# daclock-1_2.net
KiCad netlist of a schematic drawn in EAGLE
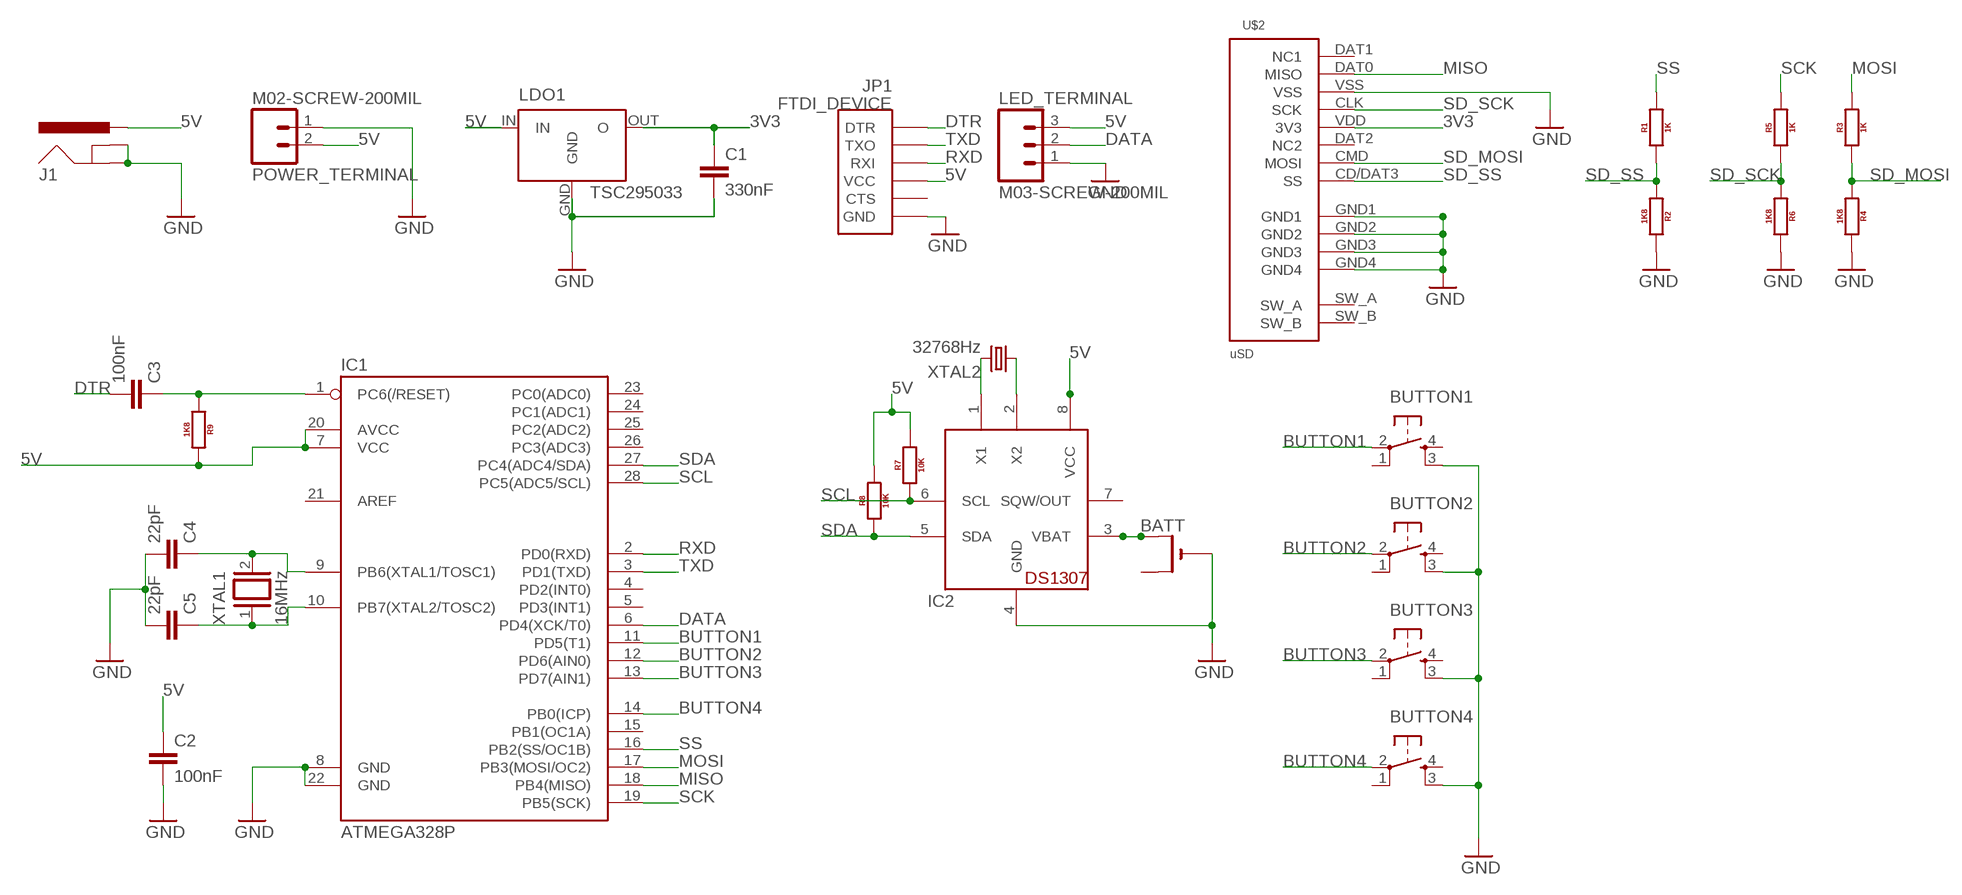
[diagram p0: schematic, sheet 1]

(export (version "E")
  (design (tool "Eeschema 10.0.6"))
  (components
    (comp (ref "BATT")
      (value "CR2032SMT")
      (footprint "eagle-import:CR2032-SMD")
      (libsource (lib "eagle-import") (part "CR2032SMT"))
    )
    (comp (ref "BUTTON1")
      (value "B1")
      (footprint "eagle-import:TACTILE_BUTTON")
      (libsource (lib "eagle-import") (part "TACTILE_BUTTON"))
    )
    (comp (ref "BUTTON2")
      (value "B2")
      (footprint "eagle-import:TACTILE_BUTTON")
      (libsource (lib "eagle-import") (part "TACTILE_BUTTON"))
    )
    (comp (ref "BUTTON3")
      (value "B3")
      (footprint "eagle-import:TACTILE_BUTTON")
      (libsource (lib "eagle-import") (part "TACTILE_BUTTON"))
    )
    (comp (ref "BUTTON4")
      (value "B4")
      (footprint "eagle-import:TACTILE_BUTTON")
      (libsource (lib "eagle-import") (part "TACTILE_BUTTON"))
    )
    (comp (ref "C1")
      (value "330nF")
      (footprint "eagle-import:C050-025X075")
      (libsource (lib "eagle-import") (part "C-EU050-025X075"))
    )
    (comp (ref "C2")
      (value "100nF")
      (footprint "eagle-import:C050-025X075")
      (libsource (lib "eagle-import") (part "C-EU050-025X075"))
    )
    (comp (ref "C3")
      (value "100nF")
      (footprint "eagle-import:C050-025X075")
      (libsource (lib "eagle-import") (part "C-EU050-025X075"))
    )
    (comp (ref "C4")
      (value "22pF")
      (footprint "eagle-import:C050-025X075")
      (libsource (lib "eagle-import") (part "C-EU050-025X075"))
    )
    (comp (ref "C5")
      (value "22pF")
      (footprint "eagle-import:C050-025X075")
      (libsource (lib "eagle-import") (part "C-EU050-025X075"))
    )
    (comp (ref "IC1")
      (value "ATMEGA328P")
      (footprint "eagle-import:DIL28-3")
      (libsource (lib "eagle-import") (part "ATMEGA328P_PDIP"))
    )
    (comp (ref "IC2")
      (value "DS1307")
      (footprint "eagle-import:DIL08")
      (libsource (lib "eagle-import") (part "DS1307"))
    )
    (comp (ref "J1")
      (value "POWER_JACKPTH")
      (footprint "eagle-import:POWER_JACK_PTH")
      (libsource (lib "eagle-import") (part "POWER_JACKPTH"))
    )
    (comp (ref "JP1")
      (value "FTDI_DEVICE")
      (footprint "eagle-import:FTDI_DEVICE_SIDE")
      (libsource (lib "eagle-import") (part "FTDI_DEVICE"))
    )
    (comp (ref "LDO1")
      (value "TSC295033")
      (footprint "eagle-import:TO92")
      (fields (field (name "MF") "NATIONAL SEMICONDUCTOR") (field (name "MPN") "LP2950CZ-5.0/NOPB"))
      (libsource (lib "eagle-import") (part "LP2950Z"))
    )
    (comp (ref "LED_TERMINAL")
      (value "M03-SCREW-200MIL")
      (footprint "eagle-import:SCREWTERMINAL-200MIL-3")
      (libsource (lib "eagle-import") (part "M03-SCREW-200MIL"))
    )
    (comp (ref "POWER_TERMINAL")
      (value "M02-SCREW-200MIL")
      (footprint "eagle-import:SCREWTERMINAL-200MIL-2")
      (libsource (lib "eagle-import") (part "M02-SCREW-200MIL"))
    )
    (comp (ref "R1")
      (value "1K")
      (footprint "eagle-import:AXIAL-0.4")
      (libsource (lib "eagle-import") (part "RESISTOR-400MIL"))
    )
    (comp (ref "R2")
      (value "1K8")
      (footprint "eagle-import:AXIAL-0.4")
      (libsource (lib "eagle-import") (part "RESISTOR-400MIL"))
    )
    (comp (ref "R3")
      (value "1K")
      (footprint "eagle-import:AXIAL-0.4")
      (libsource (lib "eagle-import") (part "RESISTOR-400MIL"))
    )
    (comp (ref "R4")
      (value "1K8")
      (footprint "eagle-import:AXIAL-0.4")
      (libsource (lib "eagle-import") (part "RESISTOR-400MIL"))
    )
    (comp (ref "R5")
      (value "1K")
      (footprint "eagle-import:AXIAL-0.4")
      (libsource (lib "eagle-import") (part "RESISTOR-400MIL"))
    )
    (comp (ref "R6")
      (value "1K8")
      (footprint "eagle-import:AXIAL-0.4")
      (libsource (lib "eagle-import") (part "RESISTOR-400MIL"))
    )
    (comp (ref "R7")
      (value "10K")
      (footprint "eagle-import:AXIAL-0.4")
      (libsource (lib "eagle-import") (part "RESISTOR-400MIL"))
    )
    (comp (ref "R8")
      (value "10K")
      (footprint "eagle-import:AXIAL-0.4")
      (libsource (lib "eagle-import") (part "RESISTOR-400MIL"))
    )
    (comp (ref "R9")
      (value "1K8")
      (footprint "eagle-import:AXIAL-0.4")
      (libsource (lib "eagle-import") (part "RESISTOR-400MIL"))
    )
    (comp (ref "U$2")
      (value "uSD")
      (footprint "eagle-import:DM3D")
      (libsource (lib "eagle-import") (part "MICROSD-HRS_DM3D"))
    )
    (comp (ref "XTAL1")
      (value "16MHz")
      (footprint "eagle-import:QS")
      (libsource (lib "eagle-import") (part "XTAL/S"))
    )
    (comp (ref "XTAL2")
      (value "32768Hz")
      (footprint "eagle-import:TC38H")
      (libsource (lib "eagle-import") (part "CRYSTAL_TC38H"))
    )
  )
  (nets
    (net (code "1") (name "/3V3") (class "Default")
      (node (ref "C1") (pin "1") (pinfunction "1_1") (pintype "passive"))
      (node (ref "LDO1") (pin "OUT") (pinfunction "O_OUT") (pintype "output"))
      (node (ref "U$2") (pin "VDD") (pinfunction "3V3_VDD") (pintype "bidirectional"))
    )
    (net (code "2") (name "/5V") (class "Default")
      (node (ref "C2") (pin "1") (pinfunction "1_1") (pintype "passive"))
      (node (ref "IC1") (pin "20") (pinfunction "AVCC_20") (pintype "bidirectional"))
      (node (ref "IC1") (pin "7") (pinfunction "VCC_7") (pintype "bidirectional"))
      (node (ref "IC2") (pin "8") (pinfunction "VCC_8") (pintype "power_in"))
      (node (ref "J1") (pin "PWR") (pinfunction "PWR_PWR") (pintype "bidirectional"))
      (node (ref "JP1") (pin "P$4") (pinfunction "VCC_P$4") (pintype "bidirectional"))
      (node (ref "LDO1") (pin "IN") (pinfunction "IN_IN") (pintype "input"))
      (node (ref "LED_TERMINAL") (pin "3") (pinfunction "3_3") (pintype "passive"))
      (node (ref "POWER_TERMINAL") (pin "2") (pinfunction "2_2") (pintype "passive"))
      (node (ref "R7") (pin "P$2") (pinfunction "2_P$2") (pintype "passive"))
      (node (ref "R8") (pin "P$2") (pinfunction "2_P$2") (pintype "passive"))
      (node (ref "R9") (pin "P$2") (pinfunction "2_P$2") (pintype "passive"))
    )
    (net (code "3") (name "/BUTTON1") (class "Default")
      (node (ref "BUTTON1") (pin "2") (pinfunction "SWA1_2") (pintype "passive"))
      (node (ref "IC1") (pin "11") (pinfunction "PD5(T1)_11") (pintype "bidirectional"))
    )
    (net (code "4") (name "/BUTTON2") (class "Default")
      (node (ref "BUTTON2") (pin "2") (pinfunction "SWA1_2") (pintype "passive"))
      (node (ref "IC1") (pin "12") (pinfunction "PD6(AIN0)_12") (pintype "bidirectional"))
    )
    (net (code "5") (name "/BUTTON3") (class "Default")
      (node (ref "BUTTON3") (pin "2") (pinfunction "SWA1_2") (pintype "passive"))
      (node (ref "IC1") (pin "13") (pinfunction "PD7(AIN1)_13") (pintype "bidirectional"))
    )
    (net (code "6") (name "/BUTTON4") (class "Default")
      (node (ref "BUTTON4") (pin "2") (pinfunction "SWA1_2") (pintype "passive"))
      (node (ref "IC1") (pin "14") (pinfunction "PB0(ICP)_14") (pintype "bidirectional"))
    )
    (net (code "7") (name "/DATA") (class "Default")
      (node (ref "IC1") (pin "6") (pinfunction "PD4(XCK/T0)_6") (pintype "bidirectional"))
      (node (ref "LED_TERMINAL") (pin "2") (pinfunction "2_2") (pintype "passive"))
    )
    (net (code "8") (name "/DTR") (class "Default")
      (node (ref "C3") (pin "2") (pinfunction "2_2") (pintype "passive"))
      (node (ref "JP1") (pin "P$1") (pinfunction "DTR_P$1") (pintype "bidirectional"))
    )
    (net (code "9") (name "/MISO") (class "Default")
      (node (ref "IC1") (pin "18") (pinfunction "PB4(MISO)_18") (pintype "bidirectional"))
      (node (ref "U$2") (pin "DAT0") (pinfunction "MISO_DAT0") (pintype "bidirectional"))
    )
    (net (code "10") (name "/MOSI") (class "Default")
      (node (ref "IC1") (pin "17") (pinfunction "PB3(MOSI/OC2)_17") (pintype "bidirectional"))
      (node (ref "R3") (pin "P$2") (pinfunction "2_P$2") (pintype "passive"))
    )
    (net (code "11") (name "/RXD") (class "Default")
      (node (ref "IC1") (pin "2") (pinfunction "PD0(RXD)_2") (pintype "bidirectional"))
      (node (ref "JP1") (pin "P$3") (pinfunction "RXI_P$3") (pintype "bidirectional"))
    )
    (net (code "12") (name "/SCK") (class "Default")
      (node (ref "IC1") (pin "19") (pinfunction "PB5(SCK)_19") (pintype "bidirectional"))
      (node (ref "R5") (pin "P$2") (pinfunction "2_P$2") (pintype "passive"))
    )
    (net (code "13") (name "/SCL") (class "Default")
      (node (ref "IC1") (pin "28") (pinfunction "PC5(ADC5/SCL)_28") (pintype "bidirectional"))
      (node (ref "IC2") (pin "6") (pinfunction "SCL_6") (pintype "bidirectional"))
      (node (ref "R7") (pin "P$1") (pinfunction "1_P$1") (pintype "passive"))
    )
    (net (code "14") (name "/SDA") (class "Default")
      (node (ref "IC1") (pin "27") (pinfunction "PC4(ADC4/SDA)_27") (pintype "bidirectional"))
      (node (ref "IC2") (pin "5") (pinfunction "SDA_5") (pintype "bidirectional"))
      (node (ref "R8") (pin "P$1") (pinfunction "1_P$1") (pintype "passive"))
    )
    (net (code "15") (name "/SD_MOSI") (class "Default")
      (node (ref "R3") (pin "P$1") (pinfunction "1_P$1") (pintype "passive"))
      (node (ref "R4") (pin "P$1") (pinfunction "1_P$1") (pintype "passive"))
      (node (ref "U$2") (pin "CMD") (pinfunction "MOSI_CMD") (pintype "bidirectional"))
    )
    (net (code "16") (name "/SD_SCK") (class "Default")
      (node (ref "R5") (pin "P$1") (pinfunction "1_P$1") (pintype "passive"))
      (node (ref "R6") (pin "P$1") (pinfunction "1_P$1") (pintype "passive"))
      (node (ref "U$2") (pin "CLK") (pinfunction "SCK_CLK") (pintype "bidirectional"))
    )
    (net (code "17") (name "/SD_SS") (class "Default")
      (node (ref "R1") (pin "P$1") (pinfunction "1_P$1") (pintype "passive"))
      (node (ref "R2") (pin "P$1") (pinfunction "1_P$1") (pintype "passive"))
      (node (ref "U$2") (pin "CD/DAT3") (pinfunction "SS_CD/DAT3") (pintype "bidirectional"))
    )
    (net (code "18") (name "/SS") (class "Default")
      (node (ref "IC1") (pin "16") (pinfunction "PB2(SS/OC1B)_16") (pintype "bidirectional"))
      (node (ref "R1") (pin "P$2") (pinfunction "2_P$2") (pintype "passive"))
    )
    (net (code "19") (name "/TXD") (class "Default")
      (node (ref "IC1") (pin "3") (pinfunction "PD1(TXD)_3") (pintype "bidirectional"))
      (node (ref "JP1") (pin "P$2") (pinfunction "TXO_P$2") (pintype "bidirectional"))
    )
    (net (code "20") (name "GND") (class "Default")
      (node (ref "BATT") (pin "-") (pinfunction "-_-") (pintype "passive"))
      (node (ref "BUTTON1") (pin "3") (pinfunction "SWB2_3") (pintype "passive"))
      (node (ref "BUTTON2") (pin "3") (pinfunction "SWB2_3") (pintype "passive"))
      (node (ref "BUTTON3") (pin "3") (pinfunction "SWB2_3") (pintype "passive"))
      (node (ref "BUTTON4") (pin "3") (pinfunction "SWB2_3") (pintype "passive"))
      (node (ref "C1") (pin "2") (pinfunction "2_2") (pintype "passive"))
      (node (ref "C2") (pin "2") (pinfunction "2_2") (pintype "passive"))
      (node (ref "C4") (pin "2") (pinfunction "2_2") (pintype "passive"))
      (node (ref "C5") (pin "2") (pinfunction "2_2") (pintype "passive"))
      (node (ref "IC1") (pin "22") (pinfunction "GND_22") (pintype "bidirectional"))
      (node (ref "IC1") (pin "8") (pinfunction "GND_8") (pintype "bidirectional"))
      (node (ref "IC2") (pin "4") (pinfunction "GND_4") (pintype "power_in"))
      (node (ref "J1") (pin "GND") (pinfunction "GND_GND") (pintype "bidirectional"))
      (node (ref "J1") (pin "GNDBREAK") (pinfunction "GNDBREAK_GNDBREAK") (pintype "bidirectional"))
      (node (ref "JP1") (pin "P$6") (pinfunction "GND_P$6") (pintype "bidirectional"))
      (node (ref "LDO1") (pin "GND") (pinfunction "GND_GND") (pintype "power_in"))
      (node (ref "LED_TERMINAL") (pin "1") (pinfunction "1_1") (pintype "passive"))
      (node (ref "POWER_TERMINAL") (pin "1") (pinfunction "1_1") (pintype "passive"))
      (node (ref "R2") (pin "P$2") (pinfunction "2_P$2") (pintype "passive"))
      (node (ref "R4") (pin "P$2") (pinfunction "2_P$2") (pintype "passive"))
      (node (ref "R6") (pin "P$2") (pinfunction "2_P$2") (pintype "passive"))
      (node (ref "U$2") (pin "GND1") (pinfunction "GND1_GND1") (pintype "bidirectional"))
      (node (ref "U$2") (pin "GND2") (pinfunction "GND2_GND2") (pintype "bidirectional"))
      (node (ref "U$2") (pin "GND3") (pinfunction "GND3_GND3") (pintype "bidirectional"))
      (node (ref "U$2") (pin "GND4") (pinfunction "GND4_GND4") (pintype "bidirectional"))
      (node (ref "U$2") (pin "VSS") (pinfunction "VSS_VSS") (pintype "bidirectional"))
    )
    (net (code "21") (name "Net-(BATT-+)") (class "Default")
      (node (ref "BATT") (pin "+$1") (pinfunction "+_+$1") (pintype "passive"))
      (node (ref "IC2") (pin "3") (pinfunction "VBAT_3") (pintype "power_in"))
    )
    (net (code "22") (name "Net-(IC1-PB6(XTAL1{slash}TOSC1))") (class "Default")
      (node (ref "C4") (pin "1") (pinfunction "1_1") (pintype "passive"))
      (node (ref "IC1") (pin "9") (pinfunction "PB6(XTAL1/TOSC1)_9") (pintype "bidirectional"))
      (node (ref "XTAL1") (pin "2") (pinfunction "2_2") (pintype "passive"))
    )
    (net (code "23") (name "Net-(IC1-PB7(XTAL2{slash}TOSC2))") (class "Default")
      (node (ref "C5") (pin "1") (pinfunction "1_1") (pintype "passive"))
      (node (ref "IC1") (pin "10") (pinfunction "PB7(XTAL2/TOSC2)_10") (pintype "bidirectional"))
      (node (ref "XTAL1") (pin "1") (pinfunction "1_1") (pintype "passive"))
    )
    (net (code "24") (name "Net-(IC1-PC6({slash}RESET))") (class "Default")
      (node (ref "C3") (pin "1") (pinfunction "1_1") (pintype "passive"))
      (node (ref "IC1") (pin "1") (pinfunction "PC6(/RESET)_1") (pintype "bidirectional"))
      (node (ref "R9") (pin "P$1") (pinfunction "1_P$1") (pintype "passive"))
    )
    (net (code "25") (name "Net-(IC2-X1)") (class "Default")
      (node (ref "IC2") (pin "1") (pinfunction "X1_1") (pintype "passive"))
      (node (ref "XTAL2") (pin "2") (pinfunction "2_2") (pintype "passive"))
    )
    (net (code "26") (name "Net-(IC2-X2)") (class "Default")
      (node (ref "IC2") (pin "2") (pinfunction "X2_2") (pintype "passive"))
      (node (ref "XTAL2") (pin "1") (pinfunction "1_1") (pintype "passive"))
    )
    (net (code "27") (name "unconnected-(BATT-+1-Pad+$2)") (class "Default")
      (node (ref "BATT") (pin "+$2") (pinfunction "+1_+$2") (pintype "passive"))
    )
    (net (code "28") (name "unconnected-(BUTTON1-SWA2-Pad4)") (class "Default")
      (node (ref "BUTTON1") (pin "4") (pinfunction "SWA2_4") (pintype "passive"))
    )
    (net (code "29") (name "unconnected-(BUTTON1-SWB1-Pad1)") (class "Default")
      (node (ref "BUTTON1") (pin "1") (pinfunction "SWB1_1") (pintype "passive"))
    )
    (net (code "30") (name "unconnected-(BUTTON2-SWA2-Pad4)") (class "Default")
      (node (ref "BUTTON2") (pin "4") (pinfunction "SWA2_4") (pintype "passive"))
    )
    (net (code "31") (name "unconnected-(BUTTON2-SWB1-Pad1)") (class "Default")
      (node (ref "BUTTON2") (pin "1") (pinfunction "SWB1_1") (pintype "passive"))
    )
    (net (code "32") (name "unconnected-(BUTTON3-SWA2-Pad4)") (class "Default")
      (node (ref "BUTTON3") (pin "4") (pinfunction "SWA2_4") (pintype "passive"))
    )
    (net (code "33") (name "unconnected-(BUTTON3-SWB1-Pad1)") (class "Default")
      (node (ref "BUTTON3") (pin "1") (pinfunction "SWB1_1") (pintype "passive"))
    )
    (net (code "34") (name "unconnected-(BUTTON4-SWA2-Pad4)") (class "Default")
      (node (ref "BUTTON4") (pin "4") (pinfunction "SWA2_4") (pintype "passive"))
    )
    (net (code "35") (name "unconnected-(BUTTON4-SWB1-Pad1)") (class "Default")
      (node (ref "BUTTON4") (pin "1") (pinfunction "SWB1_1") (pintype "passive"))
    )
    (net (code "36") (name "unconnected-(IC1-AREF-Pad21)") (class "Default")
      (node (ref "IC1") (pin "21") (pinfunction "AREF_21") (pintype "bidirectional"))
    )
    (net (code "37") (name "unconnected-(IC1-PB1(OC1A)-Pad15)") (class "Default")
      (node (ref "IC1") (pin "15") (pinfunction "PB1(OC1A)_15") (pintype "bidirectional"))
    )
    (net (code "38") (name "unconnected-(IC1-PC0(ADC0)-Pad23)") (class "Default")
      (node (ref "IC1") (pin "23") (pinfunction "PC0(ADC0)_23") (pintype "bidirectional"))
    )
    (net (code "39") (name "unconnected-(IC1-PC1(ADC1)-Pad24)") (class "Default")
      (node (ref "IC1") (pin "24") (pinfunction "PC1(ADC1)_24") (pintype "bidirectional"))
    )
    (net (code "40") (name "unconnected-(IC1-PC2(ADC2)-Pad25)") (class "Default")
      (node (ref "IC1") (pin "25") (pinfunction "PC2(ADC2)_25") (pintype "bidirectional"))
    )
    (net (code "41") (name "unconnected-(IC1-PC3(ADC3)-Pad26)") (class "Default")
      (node (ref "IC1") (pin "26") (pinfunction "PC3(ADC3)_26") (pintype "bidirectional"))
    )
    (net (code "42") (name "unconnected-(IC1-PD2(INT0)-Pad4)") (class "Default")
      (node (ref "IC1") (pin "4") (pinfunction "PD2(INT0)_4") (pintype "bidirectional"))
    )
    (net (code "43") (name "unconnected-(IC1-PD3(INT1)-Pad5)") (class "Default")
      (node (ref "IC1") (pin "5") (pinfunction "PD3(INT1)_5") (pintype "bidirectional"))
    )
    (net (code "44") (name "unconnected-(IC2-SQW{slash}OUT-Pad7)") (class "Default")
      (node (ref "IC2") (pin "7") (pinfunction "SQW/OUT_7") (pintype "bidirectional"))
    )
    (net (code "45") (name "unconnected-(JP1-CTS-PadP$5)") (class "Default")
      (node (ref "JP1") (pin "P$5") (pinfunction "CTS_P$5") (pintype "bidirectional"))
    )
    (net (code "46") (name "unconnected-(U$2-NC1-PadDAT1)") (class "Default")
      (node (ref "U$2") (pin "DAT1") (pinfunction "NC1_DAT1") (pintype "bidirectional"))
    )
    (net (code "47") (name "unconnected-(U$2-NC2-PadDAT2)") (class "Default")
      (node (ref "U$2") (pin "DAT2") (pinfunction "NC2_DAT2") (pintype "bidirectional"))
    )
    (net (code "48") (name "unconnected-(U$2-PadSW_A)") (class "Default")
      (node (ref "U$2") (pin "SW_A") (pinfunction "SW_A_SW_A") (pintype "bidirectional"))
    )
    (net (code "49") (name "unconnected-(U$2-PadSW_B)") (class "Default")
      (node (ref "U$2") (pin "SW_B") (pinfunction "SW_B_SW_B") (pintype "bidirectional"))
    )
  )
)
